# Peripherals.net
KiCad netlist of a schematic drawn in Altium Designer
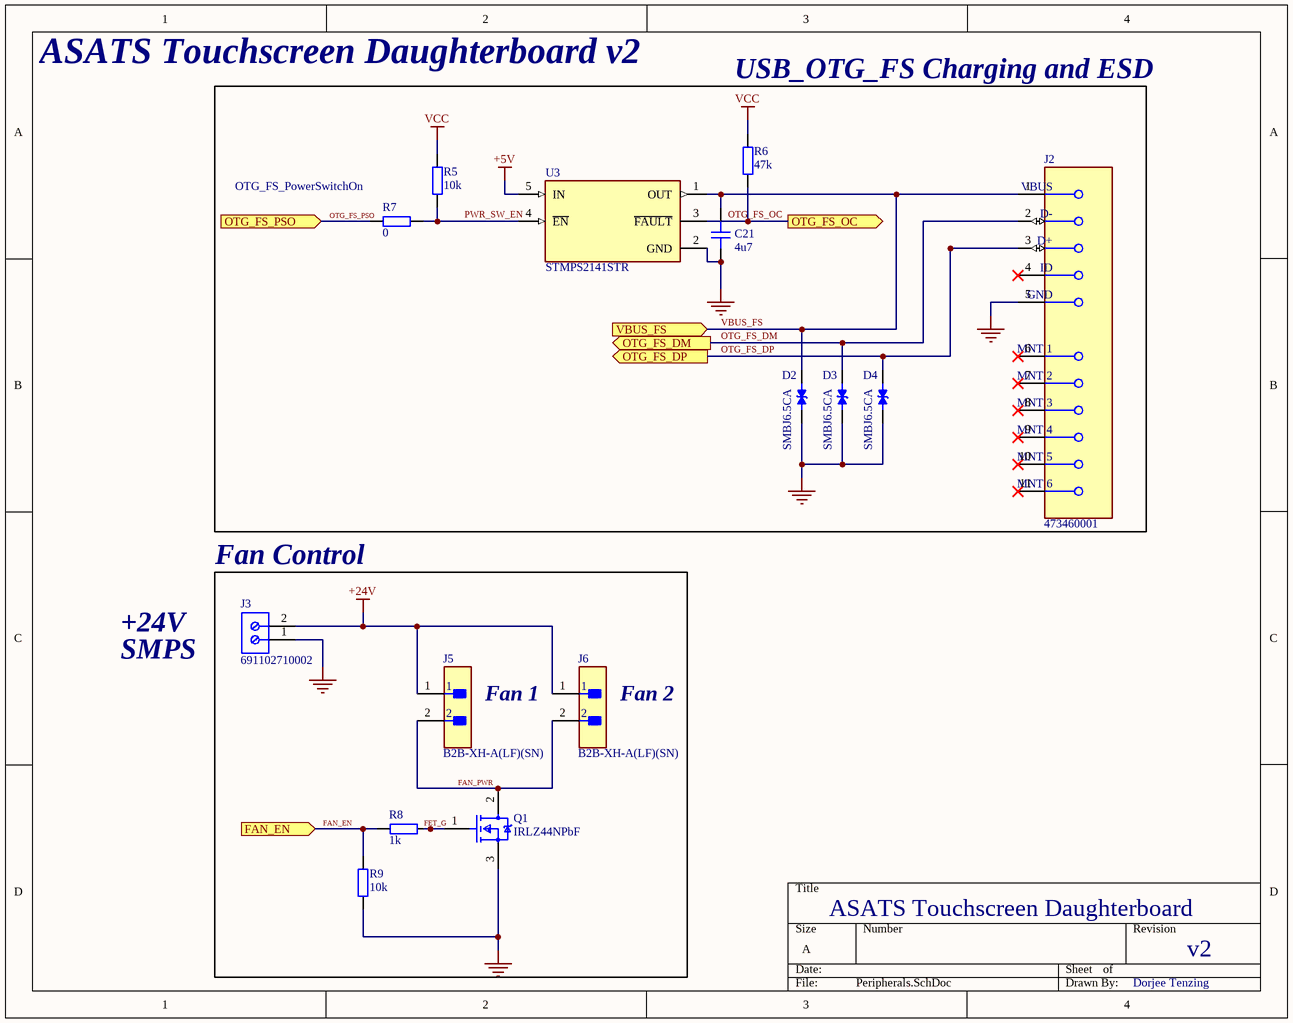
[diagram p0: Peripherals.SchDoc]

(export (version "E")
  (design (tool "Eeschema 10.0.6"))
  (components
    (comp (ref "C21")
      (value "4u7")
      (footprint "CAP_0603")
      (description "Capacitor SMD 0603")
      (fields
        (field (name "MANUFACTURER") "Samsung Electro-Mechanics")
        (field (name "MANUFACTURER PART NUMBER") "CL10A475KO8NNNC")
      )
      (libsource (lib "Schematic-Lib-PhilsLab") (part "CAP_0603"))
    )
    (comp (ref "D2")
      (value "SMBJ6.5CA")
      (footprint "DIOM4336X265N")
      (description "53.57A 600W 11.2V 7.22V Bidirectional 6.5V SMB  ESD and Surge Protection (TVS/ESD) ROHS")
      (fields (field (name "MANUFACTURER") "hongjiacheng"))
      (libsource (lib "MySymbols") (part "SMBJ6.5CA"))
    )
    (comp (ref "D3")
      (value "SMBJ6.5CA")
      (footprint "DIOM4336X265N")
      (description "53.57A 600W 11.2V 7.22V Bidirectional 6.5V SMB  ESD and Surge Protection (TVS/ESD) ROHS")
      (fields (field (name "MANUFACTURER") "hongjiacheng"))
      (libsource (lib "MySymbols") (part "SMBJ6.5CA"))
    )
    (comp (ref "D4")
      (value "SMBJ6.5CA")
      (footprint "DIOM4336X265N")
      (description "53.57A 600W 11.2V 7.22V Bidirectional 6.5V SMB  ESD and Surge Protection (TVS/ESD) ROHS")
      (fields (field (name "MANUFACTURER") "hongjiacheng"))
      (libsource (lib "MySymbols") (part "SMBJ6.5CA"))
    )
    (comp (ref "J2")
      (value "473460001")
      (footprint "FP-473460001-MFG")
      (description "CONN RCPT USB2.0 MICRO B SMD R/A")
      (fields
        (field (name "OCTOPART") "https://octopart.com/47346-0001-molex-7164928")
        (field (name "MANUFACTURER") "Molex")
      )
      (libsource (lib "Altium Content Vault") (part "53ae1f1d9b557310b43ca686e5bb76a"))
    )
    (comp (ref "J3")
      (value "691102710002")
      (footprint "691102710002")
      (fields (field (name "VOLTAGE") "300V"))
      (libsource (lib "Altium Content Vault") (part "TBL - 1R - 02P - Screw"))
    )
    (comp (ref "J5")
      (value "B2B-XH-A(LF)(SN)")
      (footprint "FP-B2B-XH-A_LF_SN-MFG")
      (description "CONN HEADER VERT 2POS 2.5MM")
      (libsource (lib "Altium Content Vault") (part "3bc925449376181038e59eaffc5286c"))
    )
    (comp (ref "J6")
      (value "B2B-XH-A(LF)(SN)")
      (footprint "FP-B2B-XH-A_LF_SN-MFG")
      (description "CONN HEADER VERT 2POS 2.5MM")
      (libsource (lib "Altium Content Vault") (part "3bc925449376181038e59eaffc5286c"))
    )
    (comp (ref "Q1")
      (value "IRLZ44NPbF")
      (footprint "FP-PG-TO220-3-MFG")
      (description "MOSFET N-CH 55V 47A TO220AB")
      (libsource (lib "Altium Content Vault") (part "b09f7f152735e370c1ea22a33fa83d6"))
    )
    (comp (ref "R5")
      (value "10k")
      (footprint "RES_0402")
      (description "Resistor SMD 0402")
      (fields
        (field (name "MANUFACTURER") "UNI-ROYAL(Uniroyal Elec)")
        (field (name "MANUFACTURER PART NUMBER") "0402WGF1002TCE")
      )
      (libsource (lib "Schematic-Lib-PhilsLab") (part "RES_0402"))
    )
    (comp (ref "R6")
      (value "47k")
      (footprint "RES_0402")
      (description "Resistor SMD 0402")
      (fields
        (field (name "MANUFACTURER") "UNI-ROYAL(Uniroyal Elec)")
        (field (name "MANUFACTURER PART NUMBER") "0402WGF4702TCE")
      )
      (libsource (lib "Schematic-Lib-PhilsLab") (part "RES_0402"))
    )
    (comp (ref "R7")
      (value "0")
      (footprint "RES_0402")
      (description "Resistor SMD 0402")
      (fields
        (field (name "MANUFACTURER") "UNI-ROYAL(Uniroyal Elec)")
        (field (name "MANUFACTURER PART NUMBER") "0402WGF0000TCE")
      )
      (libsource (lib "Schematic-Lib-PhilsLab") (part "RES_0402"))
    )
    (comp (ref "R8")
      (value "1k")
      (footprint "RES_0402")
      (description "Resistor SMD 0402")
      (fields
        (field (name "MANUFACTURER") "UNI-ROYAL(Uniroyal Elec)")
        (field (name "MANUFACTURER PART NUMBER") "0402WGF1001TCE")
      )
      (libsource (lib "Schematic-Lib-PhilsLab") (part "RES_0402"))
    )
    (comp (ref "R9")
      (value "10k")
      (footprint "RES_0402")
      (description "Resistor SMD 0402")
      (fields
        (field (name "MANUFACTURER") "UNI-ROYAL(Uniroyal Elec)")
        (field (name "MANUFACTURER PART NUMBER") "0402WGF1002TCE")
      )
      (libsource (lib "Schematic-Lib-PhilsLab") (part "RES_0402"))
    )
    (comp (ref "U3")
      (value "STMPS2141STR")
      (footprint "FP-SOT23-5L-MFG")
      (description "STMPS2141STR STMPS Series 1 Channel 5.5 V 500 mA 200 mOhm High Side Power Switch - SOT-23-5")
      (fields (field (name "VOLTAGE") "5.5V") (field (name "MANUFACTURER") "STMicroelectronics"))
      (libsource (lib "Altium Content Vault") (part "dcdbc575d070b0201d64222148af8d2"))
    )
  )
  (nets
    (net (code "1") (name "+5V") (class "Default")
      (node (ref "U3") (pin "5") (pinfunction "IN_5") (pintype "input"))
    )
    (net (code "2") (name "+24V") (class "Default")
      (node (ref "J3") (pin "2") (pinfunction "2_2") (pintype "passive"))
      (node (ref "J5") (pin "1") (pinfunction "1_1") (pintype "passive"))
      (node (ref "J6") (pin "1") (pinfunction "1_1") (pintype "passive"))
    )
    (net (code "4") (name "/FAN_EN") (class "Default")
      (node (ref "R8") (pin "1") (pinfunction "1_1") (pintype "passive"))
      (node (ref "R9") (pin "2") (pinfunction "2_2") (pintype "passive"))
    )
    (net (code "5") (name "/FAN_PWR") (class "Default")
      (node (ref "J5") (pin "2") (pinfunction "2_2") (pintype "passive"))
      (node (ref "J6") (pin "2") (pinfunction "2_2") (pintype "passive"))
      (node (ref "Q1") (pin "2") (pinfunction "D_2") (pintype "passive"))
    )
    (net (code "6") (name "/FET_G") (class "Default")
      (node (ref "Q1") (pin "1") (pinfunction "G_1") (pintype "passive"))
      (node (ref "R8") (pin "2") (pinfunction "2_2") (pintype "passive"))
    )
    (net (code "7") (name "/OTG_FS_DM") (class "Default")
      (node (ref "D3") (pin "2") (pinfunction "2_2") (pintype "passive"))
      (node (ref "J2") (pin "2") (pinfunction "D-_2") (pintype "bidirectional"))
    )
    (net (code "8") (name "/OTG_FS_DP") (class "Default")
      (node (ref "D4") (pin "2") (pinfunction "2_2") (pintype "passive"))
      (node (ref "J2") (pin "3") (pinfunction "D+_3") (pintype "bidirectional"))
    )
    (net (code "9") (name "/OTG_FS_OC") (class "Default")
      (node (ref "R6") (pin "1") (pinfunction "1_1") (pintype "passive"))
      (node (ref "U3") (pin "3") (pinfunction "~{FAULT}_3") (pintype "open_collector"))
    )
    (net (code "10") (name "/OTG_FS_PSO") (class "Default")
      (node (ref "R7") (pin "1") (pinfunction "1_1") (pintype "passive"))
    )
    (net (code "11") (name "/PWR_SW_EN") (class "Default")
      (node (ref "R5") (pin "1") (pinfunction "1_1") (pintype "passive"))
      (node (ref "R7") (pin "2") (pinfunction "2_2") (pintype "passive"))
      (node (ref "U3") (pin "4") (pinfunction "~{EN}_4") (pintype "input"))
    )
    (net (code "12") (name "/VBUS_FS") (class "Default")
      (node (ref "C21") (pin "2") (pinfunction "2_2") (pintype "passive"))
      (node (ref "D2") (pin "2") (pinfunction "2_2") (pintype "passive"))
      (node (ref "J2") (pin "1") (pinfunction "VBUS_1") (pintype "power_in"))
      (node (ref "U3") (pin "1") (pinfunction "OUT_1") (pintype "output"))
    )
    (net (code "13") (name "GND") (class "Default")
      (node (ref "C21") (pin "1") (pinfunction "1_1") (pintype "passive"))
      (node (ref "D2") (pin "1") (pinfunction "1_1") (pintype "passive"))
      (node (ref "D3") (pin "1") (pinfunction "1_1") (pintype "passive"))
      (node (ref "D4") (pin "1") (pinfunction "1_1") (pintype "passive"))
      (node (ref "J2") (pin "5") (pinfunction "GND_5") (pintype "power_in"))
      (node (ref "J3") (pin "1") (pinfunction "1_1") (pintype "passive"))
      (node (ref "Q1") (pin "3") (pinfunction "S_3") (pintype "passive"))
      (node (ref "R9") (pin "1") (pinfunction "1_1") (pintype "passive"))
      (node (ref "U3") (pin "2") (pinfunction "GND_2") (pintype "power_in"))
    )
    (net (code "14") (name "VCC") (class "Default")
      (node (ref "R5") (pin "2") (pinfunction "2_2") (pintype "passive"))
      (node (ref "R6") (pin "2") (pinfunction "2_2") (pintype "passive"))
    )
    (net (code "15") (name "unconnected-(J2-ID-Pad4)") (class "Default")
      (node (ref "J2") (pin "4") (pinfunction "ID_4") (pintype "passive+no_connect"))
    )
    (net (code "16") (name "unconnected-(J2-MNT_1-Pad6)") (class "Default")
      (node (ref "J2") (pin "6") (pinfunction "MNT_1_6") (pintype "passive+no_connect"))
    )
    (net (code "17") (name "unconnected-(J2-MNT_2-Pad7)") (class "Default")
      (node (ref "J2") (pin "7") (pinfunction "MNT_2_7") (pintype "passive+no_connect"))
    )
    (net (code "18") (name "unconnected-(J2-MNT_3-Pad8)") (class "Default")
      (node (ref "J2") (pin "8") (pinfunction "MNT_3_8") (pintype "passive+no_connect"))
    )
    (net (code "19") (name "unconnected-(J2-MNT_4-Pad9)") (class "Default")
      (node (ref "J2") (pin "9") (pinfunction "MNT_4_9") (pintype "passive+no_connect"))
    )
    (net (code "20") (name "unconnected-(J2-MNT_5-Pad10)") (class "Default")
      (node (ref "J2") (pin "10") (pinfunction "MNT_5_10") (pintype "passive+no_connect"))
    )
    (net (code "21") (name "unconnected-(J2-MNT_6-Pad11)") (class "Default")
      (node (ref "J2") (pin "11") (pinfunction "MNT_6_11") (pintype "passive+no_connect"))
    )
  )
)
